# NSE2020_2.net
KiCad netlist of a schematic drawn in EAGLE
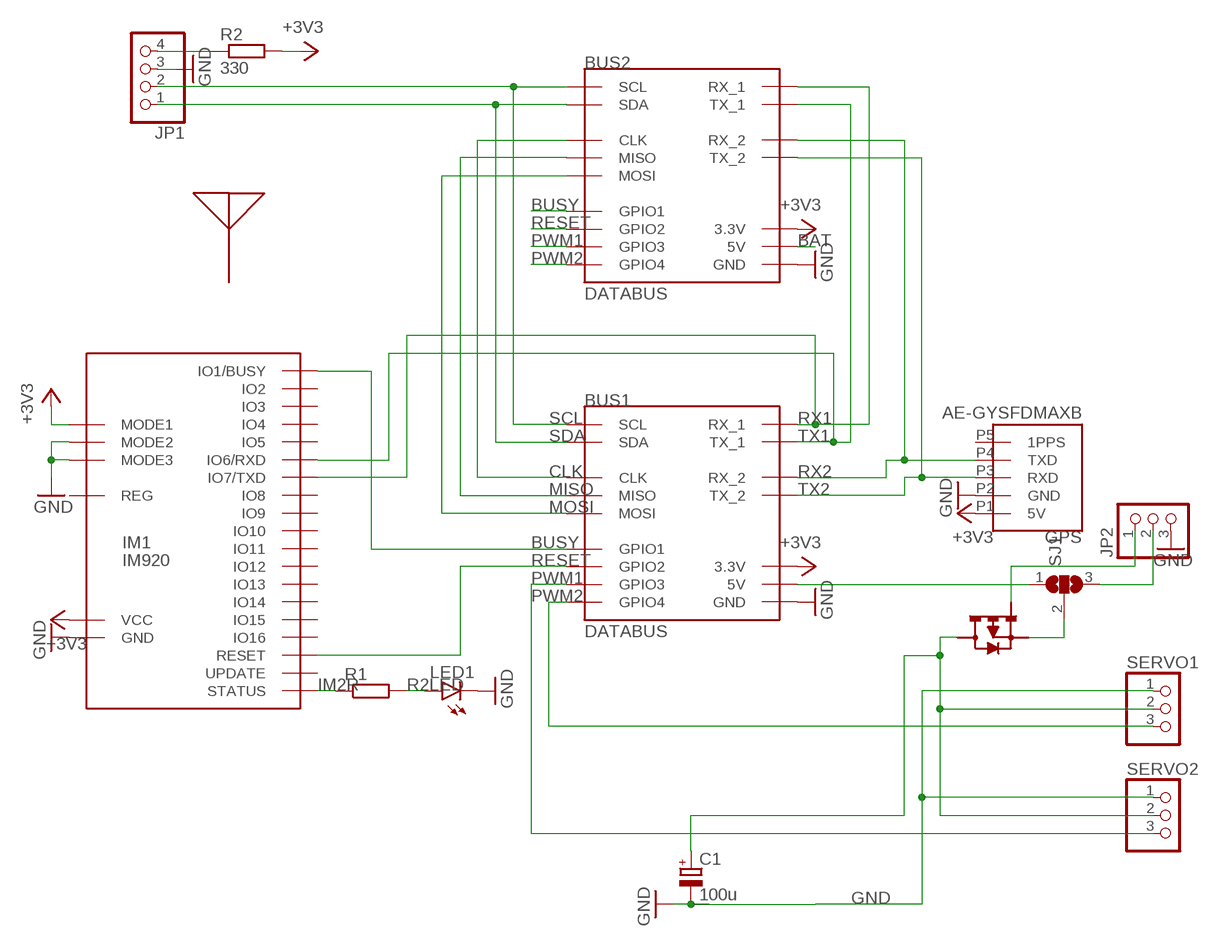
[diagram p0: schematic, sheet 1]

(export (version "E")
  (design (tool "Eeschema 10.0.6"))
  (components
    (comp (ref "ANT1")
      (value "IM920ANT-XS")
      (footprint "eagle-import:ANTENNA")
      (libsource (lib "eagle-import") (part "IM920ANT-XS"))
    )
    (comp (ref "BUS1")
      (value "DATABUS")
      (footprint "eagle-import:8X2")
      (libsource (lib "eagle-import") (part "DATABUS"))
    )
    (comp (ref "BUS2")
      (value "DATABUS")
      (footprint "eagle-import:8X2")
      (libsource (lib "eagle-import") (part "DATABUS"))
    )
    (comp (ref "C1")
      (value "100u")
      (footprint "eagle-import:E2,5-6")
      (libsource (lib "eagle-import") (part "CPOL-EUE2.5-6"))
    )
    (comp (ref "GPS")
      (value "AE-GYSFDMAXB")
      (footprint "eagle-import:AE-GYSFDMAXB")
      (libsource (lib "eagle-import") (part "AE-GYSFDMAXB"))
    )
    (comp (ref "IM1")
      (value "IM920")
      (footprint "eagle-import:IM920")
      (libsource (lib "eagle-import") (part "IM920"))
    )
    (comp (ref "JP1")
      (value "PINHD-1X4")
      (footprint "eagle-import:1X04")
      (libsource (lib "eagle-import") (part "PINHD-1X4"))
    )
    (comp (ref "JP2")
      (value "PINHD-1X3")
      (footprint "eagle-import:1X03")
      (libsource (lib "eagle-import") (part "PINHD-1X3"))
    )
    (comp (ref "LED1")
      (value "LEDSMT1206")
      (footprint "eagle-import:1206")
      (libsource (lib "eagle-import") (part "LEDSMT1206"))
    )
    (comp (ref "R1")
      (value "R-EU_M2012")
      (footprint "eagle-import:M2012")
      (libsource (lib "eagle-import") (part "R-EU_M2012"))
    )
    (comp (ref "R2")
      (value "330")
      (footprint "eagle-import:R2012")
      (libsource (lib "eagle-import") (part "R-EU_R2012"))
    )
    (comp (ref "SERVO1")
      (value "PINHD-1X3")
      (footprint "eagle-import:1X03")
      (libsource (lib "eagle-import") (part "PINHD-1X3"))
    )
    (comp (ref "SERVO2")
      (value "PINHD-1X3")
      (footprint "eagle-import:1X03")
      (libsource (lib "eagle-import") (part "PINHD-1X3"))
    )
    (comp (ref "SJ1")
      (value "SJ2W")
      (footprint "eagle-import:SJ_2")
      (libsource (lib "eagle-import") (part "SJ2W"))
    )
    (comp (ref "U$1")
      (value "2SJ681")
      (footprint "eagle-import:2SJ681")
      (libsource (lib "eagle-import") (part "2SJ681"))
    )
  )
  (nets
    (net (code "1") (name "+3V3") (class "Default")
      (node (ref "BUS1") (pin "P6") (pinfunction "3.3V_P6") (pintype "bidirectional"))
      (node (ref "BUS2") (pin "P6") (pinfunction "3.3V_P6") (pintype "bidirectional"))
      (node (ref "GPS") (pin "P1") (pinfunction "5V_P1") (pintype "bidirectional"))
      (node (ref "IM1") (pin "IO17") (pinfunction "MODE1_IO17") (pintype "bidirectional"))
      (node (ref "IM1") (pin "IO23") (pinfunction "VCC_IO23") (pintype "bidirectional"))
      (node (ref "R2") (pin "2") (pinfunction "2_2") (pintype "passive"))
    )
    (net (code "2") (name "/BAT") (class "Default")
      (node (ref "BUS2") (pin "P7") (pinfunction "5V_P7") (pintype "bidirectional"))
      (node (ref "C1") (pin "+") (pinfunction "+_+") (pintype "passive"))
      (node (ref "SERVO1") (pin "2") (pinfunction "2_2") (pintype "passive"))
      (node (ref "SERVO2") (pin "2") (pinfunction "2_2") (pintype "passive"))
      (node (ref "U$1") (pin "P$2") (pinfunction "P$1_P$2") (pintype "bidirectional"))
      (node (ref "U$1") (pin "P$4") (pinfunction "P$1_P$4") (pintype "bidirectional"))
    )
    (net (code "3") (name "/BUSY") (class "Default")
      (node (ref "BUS1") (pin "P3") (pinfunction "GPIO1_P3") (pintype "bidirectional"))
      (node (ref "BUS2") (pin "P3") (pinfunction "GPIO1_P3") (pintype "bidirectional"))
      (node (ref "IM1") (pin "IO1") (pinfunction "IO1/BUSY_IO1") (pintype "bidirectional"))
    )
    (net (code "4") (name "/CLK") (class "Default")
      (node (ref "BUS1") (pin "P1") (pinfunction "CLK_P1") (pintype "bidirectional"))
      (node (ref "BUS2") (pin "P1") (pinfunction "CLK_P1") (pintype "bidirectional"))
    )
    (net (code "5") (name "/IM2R") (class "Default")
      (node (ref "IM1") (pin "IO21") (pinfunction "STATUS_IO21") (pintype "bidirectional"))
      (node (ref "R1") (pin "1") (pinfunction "1_1") (pintype "passive"))
    )
    (net (code "6") (name "/MISO") (class "Default")
      (node (ref "BUS1") (pin "P12") (pinfunction "MISO_P12") (pintype "bidirectional"))
      (node (ref "BUS2") (pin "P12") (pinfunction "MISO_P12") (pintype "bidirectional"))
    )
    (net (code "7") (name "/MOSI") (class "Default")
      (node (ref "BUS1") (pin "P2") (pinfunction "MOSI_P2") (pintype "bidirectional"))
      (node (ref "BUS2") (pin "P2") (pinfunction "MOSI_P2") (pintype "bidirectional"))
    )
    (net (code "8") (name "/PWM1") (class "Default")
      (node (ref "BUS1") (pin "P14") (pinfunction "GPIO3_P14") (pintype "bidirectional"))
      (node (ref "BUS2") (pin "P14") (pinfunction "GPIO3_P14") (pintype "bidirectional"))
      (node (ref "SERVO2") (pin "3") (pinfunction "3_3") (pintype "passive"))
    )
    (net (code "9") (name "/PWM2") (class "Default")
      (node (ref "BUS1") (pin "P15") (pinfunction "GPIO4_P15") (pintype "bidirectional"))
      (node (ref "BUS2") (pin "P15") (pinfunction "GPIO4_P15") (pintype "bidirectional"))
      (node (ref "SERVO1") (pin "3") (pinfunction "3_3") (pintype "passive"))
    )
    (net (code "10") (name "/R2LED") (class "Default")
      (node (ref "LED1") (pin "A") (pinfunction "A_A") (pintype "passive"))
      (node (ref "R1") (pin "2") (pinfunction "2_2") (pintype "passive"))
    )
    (net (code "11") (name "/RESET") (class "Default")
      (node (ref "BUS1") (pin "P10") (pinfunction "GPIO2_P10") (pintype "bidirectional"))
      (node (ref "BUS2") (pin "P10") (pinfunction "GPIO2_P10") (pintype "bidirectional"))
      (node (ref "IM1") (pin "IO25") (pinfunction "RESET_IO25") (pintype "bidirectional"))
    )
    (net (code "12") (name "/RX1") (class "Default")
      (node (ref "BUS1") (pin "P4") (pinfunction "RX_1_P4") (pintype "bidirectional"))
      (node (ref "BUS2") (pin "P4") (pinfunction "RX_1_P4") (pintype "bidirectional"))
      (node (ref "IM1") (pin "IO7") (pinfunction "IO7/TXD_IO7") (pintype "bidirectional"))
    )
    (net (code "13") (name "/RX2") (class "Default")
      (node (ref "BUS1") (pin "P9") (pinfunction "RX_2_P9") (pintype "bidirectional"))
      (node (ref "BUS2") (pin "P9") (pinfunction "RX_2_P9") (pintype "bidirectional"))
      (node (ref "GPS") (pin "P4") (pinfunction "TXD_P4") (pintype "bidirectional"))
    )
    (net (code "14") (name "/SCL") (class "Default")
      (node (ref "BUS1") (pin "P0") (pinfunction "SCL_P0") (pintype "bidirectional"))
      (node (ref "BUS2") (pin "P0") (pinfunction "SCL_P0") (pintype "bidirectional"))
      (node (ref "JP1") (pin "2") (pinfunction "2_2") (pintype "passive"))
    )
    (net (code "15") (name "/SDA") (class "Default")
      (node (ref "BUS1") (pin "P13") (pinfunction "SDA_P13") (pintype "bidirectional"))
      (node (ref "BUS2") (pin "P13") (pinfunction "SDA_P13") (pintype "bidirectional"))
      (node (ref "JP1") (pin "1") (pinfunction "1_1") (pintype "passive"))
    )
    (net (code "16") (name "/TX1") (class "Default")
      (node (ref "BUS1") (pin "P5") (pinfunction "TX_1_P5") (pintype "bidirectional"))
      (node (ref "BUS2") (pin "P5") (pinfunction "TX_1_P5") (pintype "bidirectional"))
      (node (ref "IM1") (pin "IO6") (pinfunction "IO6/RXD_IO6") (pintype "bidirectional"))
    )
    (net (code "17") (name "/TX2") (class "Default")
      (node (ref "BUS1") (pin "P8") (pinfunction "TX_2_P8") (pintype "bidirectional"))
      (node (ref "BUS2") (pin "P8") (pinfunction "TX_2_P8") (pintype "bidirectional"))
      (node (ref "GPS") (pin "P3") (pinfunction "RXD_P3") (pintype "bidirectional"))
    )
    (net (code "18") (name "GND") (class "Default")
      (node (ref "BUS1") (pin "P11") (pinfunction "GND_P11") (pintype "bidirectional"))
      (node (ref "BUS2") (pin "P11") (pinfunction "GND_P11") (pintype "bidirectional"))
      (node (ref "C1") (pin "-") (pinfunction "-_-") (pintype "passive"))
      (node (ref "GPS") (pin "P2") (pinfunction "GND_P2") (pintype "bidirectional"))
      (node (ref "IM1") (pin "IO18") (pinfunction "MODE2_IO18") (pintype "bidirectional"))
      (node (ref "IM1") (pin "IO19") (pinfunction "MODE3_IO19") (pintype "bidirectional"))
      (node (ref "IM1") (pin "IO24") (pinfunction "GND_IO24") (pintype "bidirectional"))
      (node (ref "JP1") (pin "3") (pinfunction "3_3") (pintype "passive"))
      (node (ref "JP2") (pin "3") (pinfunction "3_3") (pintype "passive"))
      (node (ref "LED1") (pin "C") (pinfunction "C_C") (pintype "passive"))
      (node (ref "SERVO1") (pin "1") (pinfunction "1_1") (pintype "passive"))
      (node (ref "SERVO2") (pin "1") (pinfunction "1_1") (pintype "passive"))
    )
    (net (code "19") (name "Net-(BUS1-5V)") (class "Default")
      (node (ref "BUS1") (pin "P7") (pinfunction "5V_P7") (pintype "bidirectional"))
      (node (ref "SJ1") (pin "1") (pinfunction "1_1") (pintype "passive"))
    )
    (net (code "20") (name "Net-(JP1-Pad4)") (class "Default")
      (node (ref "JP1") (pin "4") (pinfunction "4_4") (pintype "passive"))
      (node (ref "R2") (pin "1") (pinfunction "1_1") (pintype "passive"))
    )
    (net (code "21") (name "Net-(JP2-Pad2)") (class "Default")
      (node (ref "JP2") (pin "2") (pinfunction "2_2") (pintype "passive"))
      (node (ref "SJ1") (pin "3") (pinfunction "3_3") (pintype "passive"))
    )
    (net (code "22") (name "Net-(SJ1-Pad2)") (class "Default")
      (node (ref "SJ1") (pin "2") (pinfunction "2_2") (pintype "passive"))
      (node (ref "U$1") (pin "P$3") (pinfunction "P$3_P$3") (pintype "bidirectional"))
    )
    (net (code "23") (name "Net-(U$1-P$2)") (class "Default")
      (node (ref "JP2") (pin "1") (pinfunction "1_1") (pintype "passive"))
      (node (ref "U$1") (pin "P$1") (pinfunction "P$2_P$1") (pintype "bidirectional"))
    )
    (net (code "24") (name "unconnected-(GPS-1PPS-PadP5)") (class "Default")
      (node (ref "GPS") (pin "P5") (pinfunction "1PPS_P5") (pintype "bidirectional"))
    )
    (net (code "25") (name "unconnected-(IM1-PadIO2)") (class "Default")
      (node (ref "IM1") (pin "IO2") (pinfunction "IO2_IO2") (pintype "bidirectional"))
    )
    (net (code "26") (name "unconnected-(IM1-PadIO3)") (class "Default")
      (node (ref "IM1") (pin "IO3") (pinfunction "IO3_IO3") (pintype "bidirectional"))
    )
    (net (code "27") (name "unconnected-(IM1-PadIO4)") (class "Default")
      (node (ref "IM1") (pin "IO4") (pinfunction "IO4_IO4") (pintype "bidirectional"))
    )
    (net (code "28") (name "unconnected-(IM1-PadIO5)") (class "Default")
      (node (ref "IM1") (pin "IO5") (pinfunction "IO5_IO5") (pintype "bidirectional"))
    )
    (net (code "29") (name "unconnected-(IM1-PadIO8)") (class "Default")
      (node (ref "IM1") (pin "IO8") (pinfunction "IO8_IO8") (pintype "bidirectional"))
    )
    (net (code "30") (name "unconnected-(IM1-PadIO9)") (class "Default")
      (node (ref "IM1") (pin "IO9") (pinfunction "IO9_IO9") (pintype "bidirectional"))
    )
    (net (code "31") (name "unconnected-(IM1-PadIO10)") (class "Default")
      (node (ref "IM1") (pin "IO10") (pinfunction "IO10_IO10") (pintype "bidirectional"))
    )
    (net (code "32") (name "unconnected-(IM1-PadIO11)") (class "Default")
      (node (ref "IM1") (pin "IO11") (pinfunction "IO11_IO11") (pintype "bidirectional"))
    )
    (net (code "33") (name "unconnected-(IM1-PadIO12)") (class "Default")
      (node (ref "IM1") (pin "IO12") (pinfunction "IO12_IO12") (pintype "bidirectional"))
    )
    (net (code "34") (name "unconnected-(IM1-PadIO13)") (class "Default")
      (node (ref "IM1") (pin "IO13") (pinfunction "IO13_IO13") (pintype "bidirectional"))
    )
    (net (code "35") (name "unconnected-(IM1-PadIO14)") (class "Default")
      (node (ref "IM1") (pin "IO14") (pinfunction "IO14_IO14") (pintype "bidirectional"))
    )
    (net (code "36") (name "unconnected-(IM1-PadIO15)") (class "Default")
      (node (ref "IM1") (pin "IO15") (pinfunction "IO15_IO15") (pintype "bidirectional"))
    )
    (net (code "37") (name "unconnected-(IM1-PadIO16)") (class "Default")
      (node (ref "IM1") (pin "IO16") (pinfunction "IO16_IO16") (pintype "bidirectional"))
    )
    (net (code "38") (name "unconnected-(IM1-REG-PadIO22)") (class "Default")
      (node (ref "IM1") (pin "IO22") (pinfunction "REG_IO22") (pintype "bidirectional"))
    )
    (net (code "39") (name "unconnected-(IM1-UPDATE-PadIO20)") (class "Default")
      (node (ref "IM1") (pin "IO20") (pinfunction "UPDATE_IO20") (pintype "bidirectional"))
    )
  )
)
